# 02_POWER.net
KiCad netlist of a schematic drawn in Altium Designer
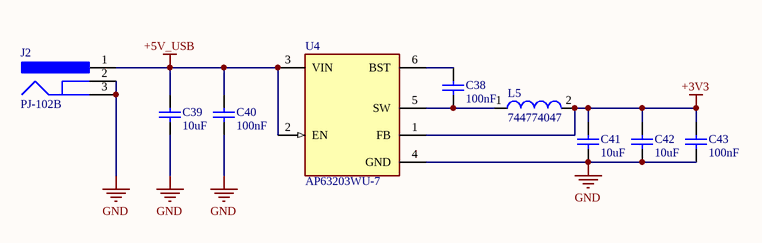
[diagram p0: 02. POWER.SchDoc]

(export (version "E")
  (design (tool "Eeschema 10.0.6"))
  (components
    (comp (ref "C38")
      (value "100nF")
      (footprint "CAPC1005X56X25NL10T15")
      (fields
        (field (name "MANUFACTURER") "AVX Interconnect / Elco")
        (field (name "PART NUMBER") "04026D104KAT2A")
      )
      (libsource (lib "Altium Content Vault") (part "CAP"))
    )
    (comp (ref "C39")
      (value "10uF")
      (footprint "CAPC1608X90X35NL10T15")
      (fields (field (name "MANUFACTURER") "Murata") (field (name "PART NUMBER") "GCM188R70J225KE22D"))
      (libsource (lib "Altium Content Vault") (part "CAP"))
    )
    (comp (ref "C40")
      (value "100nF")
      (footprint "CAPC1005X56X25NL10T15")
      (fields
        (field (name "MANUFACTURER") "AVX Interconnect / Elco")
        (field (name "PART NUMBER") "04026D104KAT2A")
      )
      (libsource (lib "Altium Content Vault") (part "CAP"))
    )
    (comp (ref "C41")
      (value "10uF")
      (footprint "CAPC1608X90X35NL10T15")
      (fields (field (name "MANUFACTURER") "Murata") (field (name "PART NUMBER") "GCM188R70J225KE22D"))
      (libsource (lib "Altium Content Vault") (part "CAP"))
    )
    (comp (ref "C42")
      (value "10uF")
      (footprint "CAPC1608X90X35NL10T15")
      (fields (field (name "MANUFACTURER") "Murata") (field (name "PART NUMBER") "GCM188R70J225KE22D"))
      (libsource (lib "Altium Content Vault") (part "CAP"))
    )
    (comp (ref "C43")
      (value "100nF")
      (footprint "CAPC1005X56X25NL10T15")
      (fields
        (field (name "MANUFACTURER") "AVX Interconnect / Elco")
        (field (name "PART NUMBER") "04026D104KAT2A")
      )
      (libsource (lib "Altium Content Vault") (part "CAP"))
    )
    (comp (ref "J2")
      (value "PJ-102B")
      (footprint "CUI-PJ-102B_V")
      (fields (field (name "MANUFACTURER") "CUIInc."))
      (libsource (lib "Altium Content Vault") (part "JACK-2CD3-RN"))
    )
    (comp (ref "L5")
      (value "744774047")
      (footprint "WE-PD2-M")
      (description "SMD Power Inductor WE-PD2, L = 4.70 µH")
      (libsource (lib "Altium Content Vault") (part "PAS-IND-INDUCTOR-2"))
    )
    (comp (ref "U4")
      (value "AP63203WU-7")
      (footprint "FP-TSOT26-IPC_B")
      (description "IC REG BUCK 3.3V 2A TSOT26")
      (fields
        (field (name "MANUFACTURER") "Diodes Inc.")
        (field (name "OCTOPART") "https://octopart.com/ap63203wu-7-diodes+inc.-98099550")
      )
      (libsource (lib "Altium Content Vault") (part "0e61c2974d7114b43f01ef96ae2e524"))
    )
  )
  (nets
    (net (code "1") (name "+3V3") (class "Default")
      (node (ref "C41") (pin "2") (pinfunction "2_2") (pintype "passive"))
      (node (ref "C42") (pin "2") (pinfunction "2_2") (pintype "passive"))
      (node (ref "C43") (pin "2") (pinfunction "2_2") (pintype "passive"))
      (node (ref "L5") (pin "2") (pinfunction "2_2") (pintype "passive"))
      (node (ref "U4") (pin "1") (pinfunction "FB_1") (pintype "passive"))
    )
    (net (code "2") (name "+5V_USB") (class "Default")
      (node (ref "C39") (pin "2") (pinfunction "2_2") (pintype "passive"))
      (node (ref "C40") (pin "2") (pinfunction "2_2") (pintype "passive"))
      (node (ref "J2") (pin "1") (pinfunction "1_1") (pintype "passive"))
      (node (ref "U4") (pin "2") (pinfunction "EN_2") (pintype "input"))
      (node (ref "U4") (pin "3") (pinfunction "VIN_3") (pintype "power_in"))
    )
    (net (code "3") (name "GND") (class "Default")
      (node (ref "C39") (pin "1") (pinfunction "1_1") (pintype "passive"))
      (node (ref "C40") (pin "1") (pinfunction "1_1") (pintype "passive"))
      (node (ref "C41") (pin "1") (pinfunction "1_1") (pintype "passive"))
      (node (ref "C42") (pin "1") (pinfunction "1_1") (pintype "passive"))
      (node (ref "C43") (pin "1") (pinfunction "1_1") (pintype "passive"))
      (node (ref "J2") (pin "2") (pinfunction "2_2") (pintype "passive"))
      (node (ref "J2") (pin "3") (pinfunction "3_3") (pintype "passive"))
      (node (ref "U4") (pin "4") (pinfunction "GND_4") (pintype "power_in"))
    )
    (net (code "4") (name "Net-(U4-BST)") (class "Default")
      (node (ref "C38") (pin "2") (pinfunction "2_2") (pintype "passive"))
      (node (ref "U4") (pin "6") (pinfunction "BST_6") (pintype "passive"))
    )
    (net (code "5") (name "Net-(U4-SW)") (class "Default")
      (node (ref "C38") (pin "1") (pinfunction "1_1") (pintype "passive"))
      (node (ref "L5") (pin "1") (pinfunction "1_1") (pintype "passive"))
      (node (ref "U4") (pin "5") (pinfunction "SW_5") (pintype "passive"))
    )
  )
)
